# Power.net
KiCad netlist of a schematic drawn in Altium Designer
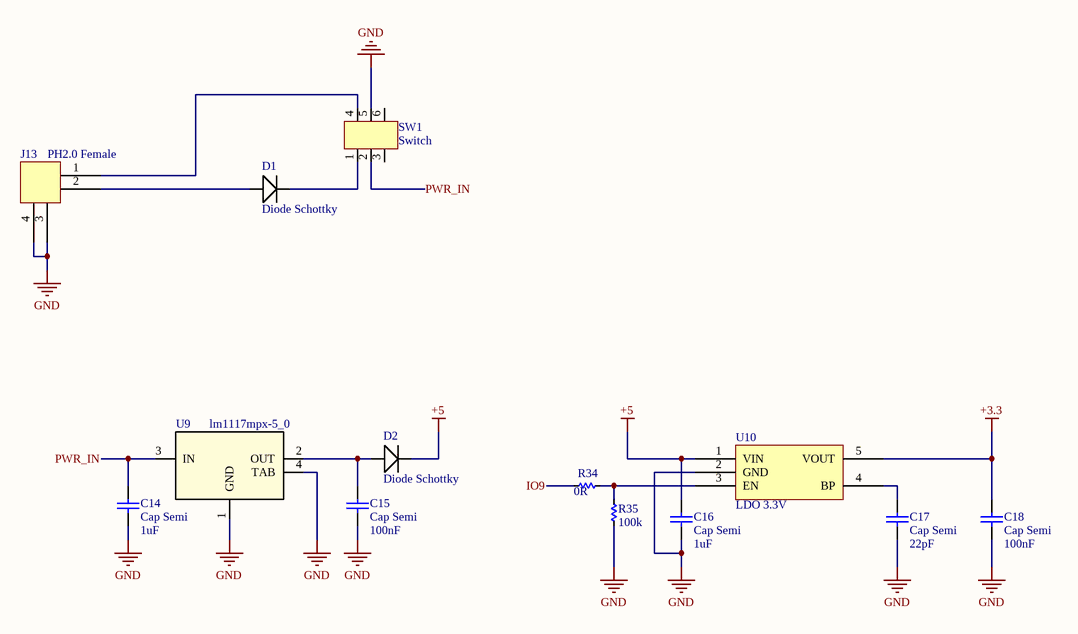
[diagram p0: Power.SchDoc]

(export (version "E")
  (design (tool "Eeschema 10.0.6"))
  (components
    (comp (ref "C14")
      (value "Cap Semi")
      (footprint "1608[0603]")
      (description "Capacitor (Semiconductor SIM Model)")
      (fields (field (name "ALTIUM_VALUE") "1uF") (field (name "PUBLISHER") "Altium Limited"))
      (libsource (lib "Miscellaneous Devices") (part "Cap Semi"))
    )
    (comp (ref "C15")
      (value "Cap Semi")
      (footprint "1608[0603]")
      (description "Capacitor (Semiconductor SIM Model)")
      (fields (field (name "ALTIUM_VALUE") "100nF") (field (name "PUBLISHER") "Altium Limited"))
      (libsource (lib "Miscellaneous Devices") (part "Cap Semi"))
    )
    (comp (ref "C16")
      (value "Cap Semi")
      (footprint "1608[0603]")
      (description "Capacitor (Semiconductor SIM Model)")
      (fields (field (name "ALTIUM_VALUE") "1uF") (field (name "PUBLISHER") "Altium Limited"))
      (libsource (lib "Miscellaneous Devices") (part "Cap Semi"))
    )
    (comp (ref "C17")
      (value "Cap Semi")
      (footprint "1608[0603]")
      (description "Capacitor (Semiconductor SIM Model)")
      (fields (field (name "ALTIUM_VALUE") "22pF") (field (name "PUBLISHER") "Altium Limited"))
      (libsource (lib "Miscellaneous Devices") (part "Cap Semi"))
    )
    (comp (ref "C18")
      (value "Cap Semi")
      (footprint "1608[0603]")
      (description "Capacitor (Semiconductor SIM Model)")
      (fields (field (name "ALTIUM_VALUE") "100nF") (field (name "PUBLISHER") "Altium Limited"))
      (libsource (lib "Miscellaneous Devices") (part "Cap Semi"))
    )
    (comp (ref "D1")
      (value "Diode Schottky")
      (footprint "DO-214AC")
      (description "Diode Shotky SS54 5A 40V")
      (libsource (lib "DiodeSchottky") (part "SS54 SMA"))
    )
    (comp (ref "D2")
      (value "Diode Schottky")
      (footprint "DO-214AC")
      (description "Diode Shotky SS54 5A 40V")
      (libsource (lib "DiodeSchottky") (part "SS54 SMA"))
    )
    (comp (ref "J13")
      (value "PH2.0 Female")
      (footprint "PH2.0 FEMALE")
      (description "2 Header PH 0.079\"(2.00mm) Male Pin SMD,P=2mm Wire To Board / Wire To Wire Connector ROHS")
      (libsource (lib "PH20") (part "PH2.0"))
    )
    (comp (ref "R34")
      (value "0R")
      (footprint "RES-SMD-0603")
      (description "Resistor")
      (fields
        (field (name "MANUFACTURER") "Generic Components")
        (field (name "Comment") "Res")
        (field (name "PUBLISHER") "Altium Hobart Technology Centre")
      )
      (libsource (lib "LIBRARY") (part "Res-SMD"))
    )
    (comp (ref "R35")
      (value "100k")
      (footprint "RES-SMD-0603")
      (description "Resistor")
      (fields
        (field (name "MANUFACTURER") "Generic Components")
        (field (name "Comment") "Res")
        (field (name "PUBLISHER") "Altium Hobart Technology Centre")
      )
      (libsource (lib "LIBRARY") (part "Res-SMD"))
    )
    (comp (ref "SW1")
      (value "Switch")
      (footprint "MSS-22D18")
      (description "Plugin,9.1x3.5mm Slide Switches ROHS")
      (libsource (lib "MSS-22D18") (part "MSS-22D18"))
    )
    (comp (ref "U9")
      (value "lm1117mpx-5_0")
      (footprint "LM1117")
      (description "No Description Available")
      (fields (field (name "COPYRIGHT") "Copyright (C) 2018 Accelerated Designs. All rights reserved"))
      (libsource (lib "MyLibrary-001") (part "lm1117mpx-5_0"))
    )
    (comp (ref "U10")
      (value "LDO 3.3V")
      (footprint "SOT-23-5")
      (description "300mA Fixed 3.3V SOT-23-5 Linear Voltage Regulators (LDO) ROHS")
      (libsource (lib "RT9193") (part "RT9193-33GB"))
    )
  )
  (nets
    (net (code "1") (name "+3.3") (class "Default")
      (node (ref "C18") (pin "2") (pinfunction "2_2") (pintype "passive"))
      (node (ref "U10") (pin "5") (pinfunction "VOUT_5") (pintype "passive"))
    )
    (net (code "2") (name "+5") (class "Default")
      (node (ref "C16") (pin "2") (pinfunction "2_2") (pintype "passive"))
      (node (ref "D2") (pin "1") (pinfunction "K_1") (pintype "passive"))
      (node (ref "U10") (pin "1") (pinfunction "VIN_1") (pintype "passive"))
    )
    (net (code "3") (name "/IO9") (class "Default")
      (node (ref "R34") (pin "2") (pinfunction "2_2") (pintype "passive"))
    )
    (net (code "4") (name "/PWR_IN") (class "Default")
      (node (ref "C14") (pin "2") (pinfunction "2_2") (pintype "passive"))
      (node (ref "SW1") (pin "2") (pinfunction "Pin_2_2") (pintype "passive"))
      (node (ref "U9") (pin "3") (pinfunction "IN_3") (pintype "power_in"))
    )
    (net (code "5") (name "GND") (class "Default")
      (node (ref "C14") (pin "1") (pinfunction "1_1") (pintype "passive"))
      (node (ref "C15") (pin "1") (pinfunction "1_1") (pintype "passive"))
      (node (ref "C16") (pin "1") (pinfunction "1_1") (pintype "passive"))
      (node (ref "C17") (pin "1") (pinfunction "1_1") (pintype "passive"))
      (node (ref "C18") (pin "1") (pinfunction "1_1") (pintype "passive"))
      (node (ref "J13") (pin "3") (pinfunction "Pin_3_3") (pintype "passive"))
      (node (ref "J13") (pin "4") (pinfunction "Pin_4_4") (pintype "passive"))
      (node (ref "R35") (pin "2") (pinfunction "2_2") (pintype "passive"))
      (node (ref "SW1") (pin "5") (pinfunction "Pin_5_5") (pintype "passive"))
      (node (ref "U10") (pin "2") (pinfunction "GND_2") (pintype "passive"))
      (node (ref "U9") (pin "1") (pinfunction "GND_1") (pintype "power_in"))
      (node (ref "U9") (pin "4") (pinfunction "TAB_4") (pintype "power_in"))
    )
    (net (code "6") (name "Net-(D1-A)") (class "Default")
      (node (ref "D1") (pin "2") (pinfunction "A_2") (pintype "passive"))
      (node (ref "J13") (pin "2") (pinfunction "Pin_2_2") (pintype "passive"))
    )
    (net (code "7") (name "Net-(D1-K)") (class "Default")
      (node (ref "D1") (pin "1") (pinfunction "K_1") (pintype "passive"))
      (node (ref "SW1") (pin "1") (pinfunction "Pin_1_1") (pintype "passive"))
    )
    (net (code "8") (name "Net-(D2-A)") (class "Default")
      (node (ref "C15") (pin "2") (pinfunction "2_2") (pintype "passive"))
      (node (ref "D2") (pin "2") (pinfunction "A_2") (pintype "passive"))
      (node (ref "U9") (pin "2") (pinfunction "OUT_2") (pintype "power_in"))
    )
    (net (code "9") (name "Net-(J13-Pin_1)") (class "Default")
      (node (ref "J13") (pin "1") (pinfunction "Pin_1_1") (pintype "passive"))
      (node (ref "SW1") (pin "4") (pinfunction "Pin_4_4") (pintype "passive"))
    )
    (net (code "10") (name "Net-(U10-BP)") (class "Default")
      (node (ref "C17") (pin "2") (pinfunction "2_2") (pintype "passive"))
      (node (ref "U10") (pin "4") (pinfunction "BP_4") (pintype "passive"))
    )
    (net (code "11") (name "Net-(U10-EN)") (class "Default")
      (node (ref "R34") (pin "1") (pinfunction "1_1") (pintype "passive"))
      (node (ref "R35") (pin "1") (pinfunction "1_1") (pintype "passive"))
      (node (ref "U10") (pin "3") (pinfunction "EN_3") (pintype "passive"))
    )
    (net (code "12") (name "unconnected-(SW1-Pin_3-Pad3)") (class "Default")
      (node (ref "SW1") (pin "3") (pinfunction "Pin_3_3") (pintype "passive"))
    )
    (net (code "13") (name "unconnected-(SW1-Pin_6-Pad6)") (class "Default")
      (node (ref "SW1") (pin "6") (pinfunction "Pin_6_6") (pintype "passive"))
    )
  )
)
